# MAX232.net
KiCad netlist of a schematic drawn in Altium Designer
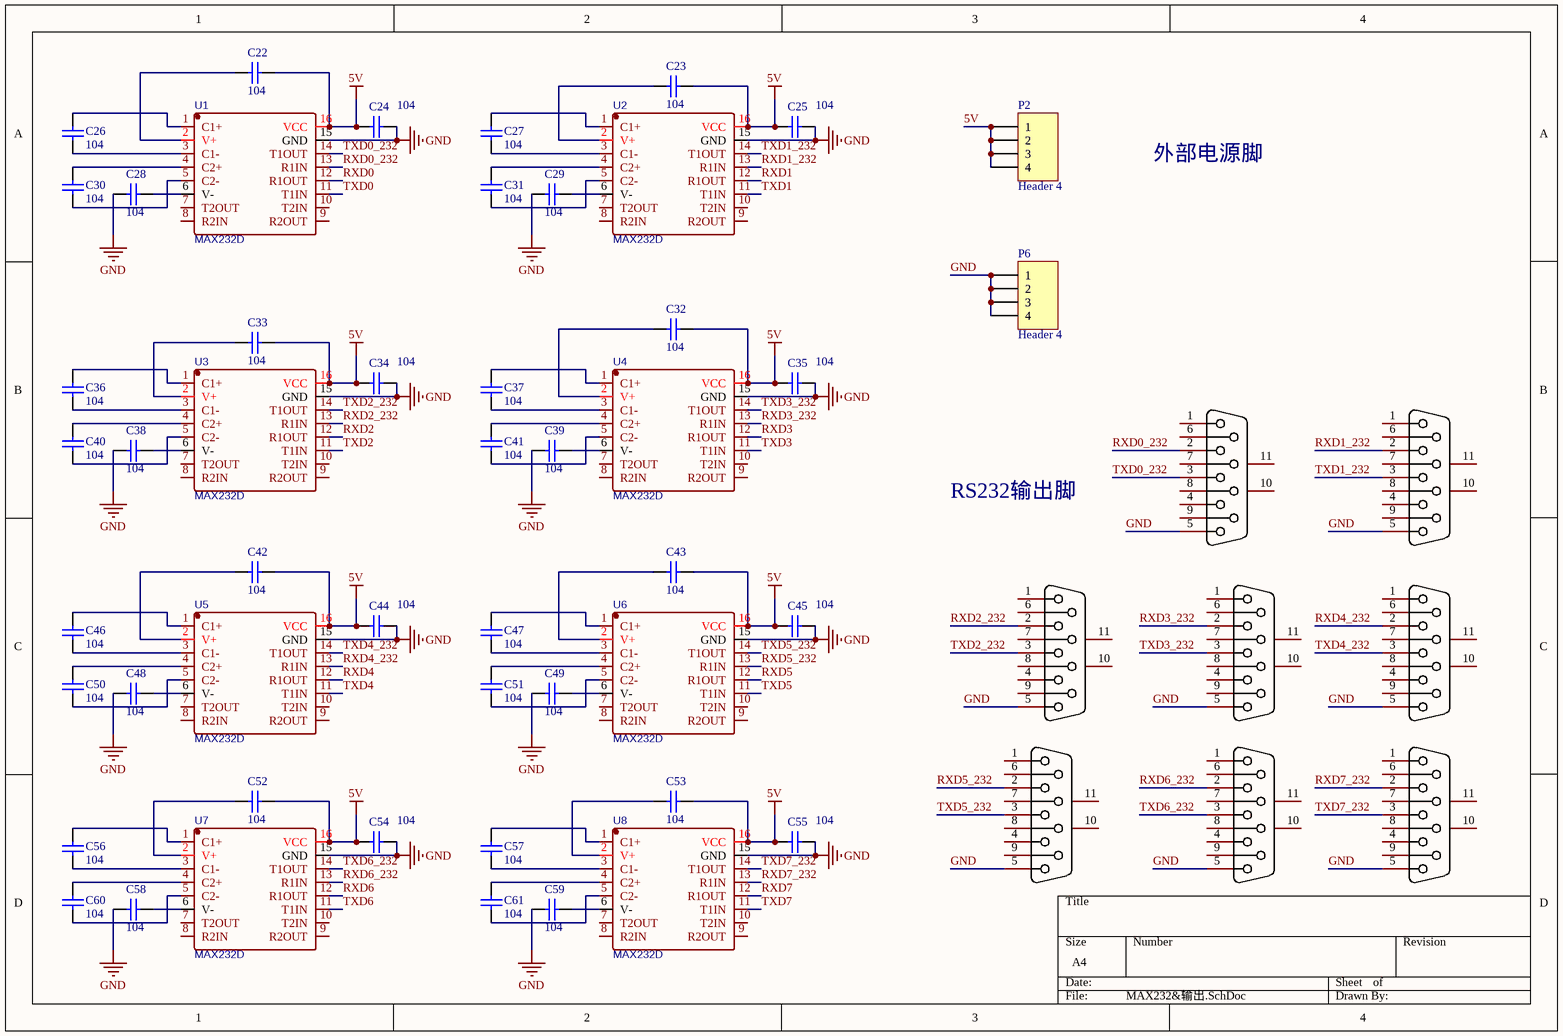
[diagram p0: MAX232&输出.SchDoc]

(export (version "E")
  (design (tool "Eeschema 10.0.6"))
  (components
    (comp (ref "C22")
      (value "104")
      (footprint "0603_C")
      (description "贴片电容")
      (libsource (lib "Miscellaneous Devices LC") (part "0603 100nF (104) 10% 50V"))
    )
    (comp (ref "C23")
      (value "104")
      (footprint "0603_C")
      (description "贴片电容")
      (libsource (lib "Miscellaneous Devices LC") (part "0603 100nF (104) 10% 50V"))
    )
    (comp (ref "C24")
      (value "104")
      (footprint "0603_C")
      (description "贴片电容")
      (libsource (lib "Miscellaneous Devices LC") (part "0603 100nF (104) 10% 50V"))
    )
    (comp (ref "C25")
      (value "104")
      (footprint "0603_C")
      (description "贴片电容")
      (libsource (lib "Miscellaneous Devices LC") (part "0603 100nF (104) 10% 50V"))
    )
    (comp (ref "C26")
      (value "104")
      (footprint "0603_C")
      (description "贴片电容")
      (libsource (lib "Miscellaneous Devices LC") (part "0603 100nF (104) 10% 50V"))
    )
    (comp (ref "C27")
      (value "104")
      (footprint "0603_C")
      (description "贴片电容")
      (libsource (lib "Miscellaneous Devices LC") (part "0603 100nF (104) 10% 50V"))
    )
    (comp (ref "C28")
      (value "104")
      (footprint "0603_C")
      (description "贴片电容")
      (libsource (lib "Miscellaneous Devices LC") (part "0603 100nF (104) 10% 50V"))
    )
    (comp (ref "C29")
      (value "104")
      (footprint "0603_C")
      (description "贴片电容")
      (libsource (lib "Miscellaneous Devices LC") (part "0603 100nF (104) 10% 50V"))
    )
    (comp (ref "C30")
      (value "104")
      (footprint "0603_C")
      (description "贴片电容")
      (libsource (lib "Miscellaneous Devices LC") (part "0603 100nF (104) 10% 50V"))
    )
    (comp (ref "C31")
      (value "104")
      (footprint "0603_C")
      (description "贴片电容")
      (libsource (lib "Miscellaneous Devices LC") (part "0603 100nF (104) 10% 50V"))
    )
    (comp (ref "C32")
      (value "104")
      (footprint "0603_C")
      (description "贴片电容")
      (libsource (lib "Miscellaneous Devices LC") (part "0603 100nF (104) 10% 50V"))
    )
    (comp (ref "C33")
      (value "104")
      (footprint "0603_C")
      (description "贴片电容")
      (libsource (lib "Miscellaneous Devices LC") (part "0603 100nF (104) 10% 50V"))
    )
    (comp (ref "C34")
      (value "104")
      (footprint "0603_C")
      (description "贴片电容")
      (libsource (lib "Miscellaneous Devices LC") (part "0603 100nF (104) 10% 50V"))
    )
    (comp (ref "C35")
      (value "104")
      (footprint "0603_C")
      (description "贴片电容")
      (libsource (lib "Miscellaneous Devices LC") (part "0603 100nF (104) 10% 50V"))
    )
    (comp (ref "C36")
      (value "104")
      (footprint "0603_C")
      (description "贴片电容")
      (libsource (lib "Miscellaneous Devices LC") (part "0603 100nF (104) 10% 50V"))
    )
    (comp (ref "C37")
      (value "104")
      (footprint "0603_C")
      (description "贴片电容")
      (libsource (lib "Miscellaneous Devices LC") (part "0603 100nF (104) 10% 50V"))
    )
    (comp (ref "C38")
      (value "104")
      (footprint "0603_C")
      (description "贴片电容")
      (libsource (lib "Miscellaneous Devices LC") (part "0603 100nF (104) 10% 50V"))
    )
    (comp (ref "C39")
      (value "104")
      (footprint "0603_C")
      (description "贴片电容")
      (libsource (lib "Miscellaneous Devices LC") (part "0603 100nF (104) 10% 50V"))
    )
    (comp (ref "C40")
      (value "104")
      (footprint "0603_C")
      (description "贴片电容")
      (libsource (lib "Miscellaneous Devices LC") (part "0603 100nF (104) 10% 50V"))
    )
    (comp (ref "C41")
      (value "104")
      (footprint "0603_C")
      (description "贴片电容")
      (libsource (lib "Miscellaneous Devices LC") (part "0603 100nF (104) 10% 50V"))
    )
    (comp (ref "C42")
      (value "104")
      (footprint "0603_C")
      (description "贴片电容")
      (libsource (lib "Miscellaneous Devices LC") (part "0603 100nF (104) 10% 50V"))
    )
    (comp (ref "C43")
      (value "104")
      (footprint "0603_C")
      (description "贴片电容")
      (libsource (lib "Miscellaneous Devices LC") (part "0603 100nF (104) 10% 50V"))
    )
    (comp (ref "C44")
      (value "104")
      (footprint "0603_C")
      (description "贴片电容")
      (libsource (lib "Miscellaneous Devices LC") (part "0603 100nF (104) 10% 50V"))
    )
    (comp (ref "C45")
      (value "104")
      (footprint "0603_C")
      (description "贴片电容")
      (libsource (lib "Miscellaneous Devices LC") (part "0603 100nF (104) 10% 50V"))
    )
    (comp (ref "C46")
      (value "104")
      (footprint "0603_C")
      (description "贴片电容")
      (libsource (lib "Miscellaneous Devices LC") (part "0603 100nF (104) 10% 50V"))
    )
    (comp (ref "C47")
      (value "104")
      (footprint "0603_C")
      (description "贴片电容")
      (libsource (lib "Miscellaneous Devices LC") (part "0603 100nF (104) 10% 50V"))
    )
    (comp (ref "C48")
      (value "104")
      (footprint "0603_C")
      (description "贴片电容")
      (libsource (lib "Miscellaneous Devices LC") (part "0603 100nF (104) 10% 50V"))
    )
    (comp (ref "C49")
      (value "104")
      (footprint "0603_C")
      (description "贴片电容")
      (libsource (lib "Miscellaneous Devices LC") (part "0603 100nF (104) 10% 50V"))
    )
    (comp (ref "C50")
      (value "104")
      (footprint "0603_C")
      (description "贴片电容")
      (libsource (lib "Miscellaneous Devices LC") (part "0603 100nF (104) 10% 50V"))
    )
    (comp (ref "C51")
      (value "104")
      (footprint "0603_C")
      (description "贴片电容")
      (libsource (lib "Miscellaneous Devices LC") (part "0603 100nF (104) 10% 50V"))
    )
    (comp (ref "C52")
      (value "104")
      (footprint "0603_C")
      (description "贴片电容")
      (libsource (lib "Miscellaneous Devices LC") (part "0603 100nF (104) 10% 50V"))
    )
    (comp (ref "C53")
      (value "104")
      (footprint "0603_C")
      (description "贴片电容")
      (libsource (lib "Miscellaneous Devices LC") (part "0603 100nF (104) 10% 50V"))
    )
    (comp (ref "C54")
      (value "104")
      (footprint "0603_C")
      (description "贴片电容")
      (libsource (lib "Miscellaneous Devices LC") (part "0603 100nF (104) 10% 50V"))
    )
    (comp (ref "C55")
      (value "104")
      (footprint "0603_C")
      (description "贴片电容")
      (libsource (lib "Miscellaneous Devices LC") (part "0603 100nF (104) 10% 50V"))
    )
    (comp (ref "C56")
      (value "104")
      (footprint "0603_C")
      (description "贴片电容")
      (libsource (lib "Miscellaneous Devices LC") (part "0603 100nF (104) 10% 50V"))
    )
    (comp (ref "C57")
      (value "104")
      (footprint "0603_C")
      (description "贴片电容")
      (libsource (lib "Miscellaneous Devices LC") (part "0603 100nF (104) 10% 50V"))
    )
    (comp (ref "C58")
      (value "104")
      (footprint "0603_C")
      (description "贴片电容")
      (libsource (lib "Miscellaneous Devices LC") (part "0603 100nF (104) 10% 50V"))
    )
    (comp (ref "C59")
      (value "104")
      (footprint "0603_C")
      (description "贴片电容")
      (libsource (lib "Miscellaneous Devices LC") (part "0603 100nF (104) 10% 50V"))
    )
    (comp (ref "C60")
      (value "104")
      (footprint "0603_C")
      (description "贴片电容")
      (libsource (lib "Miscellaneous Devices LC") (part "0603 100nF (104) 10% 50V"))
    )
    (comp (ref "C61")
      (value "104")
      (footprint "0603_C")
      (description "贴片电容")
      (libsource (lib "Miscellaneous Devices LC") (part "0603 100nF (104) 10% 50V"))
    )
    (comp (ref "DSUB1")
      (value "D-DMR009PM-D002")
      (footprint "DSUB-TH_DMR-9P")
      (fields (field (name "MANUFACTURER") "Ckmtw(灿科盟)"))
      (libsource (lib "DB9公头") (part "D-DMR009PM-D002"))
    )
    (comp (ref "DSUB2")
      (value "D-DMR009PM-D002")
      (footprint "DSUB-TH_DMR-9P")
      (fields (field (name "MANUFACTURER") "Ckmtw(灿科盟)"))
      (libsource (lib "DB9公头") (part "D-DMR009PM-D002"))
    )
    (comp (ref "DSUB3")
      (value "D-DMR009PM-D002")
      (footprint "DSUB-TH_DMR-9P")
      (fields (field (name "MANUFACTURER") "Ckmtw(灿科盟)"))
      (libsource (lib "DB9公头") (part "D-DMR009PM-D002"))
    )
    (comp (ref "DSUB4")
      (value "D-DMR009PM-D002")
      (footprint "DSUB-TH_DMR-9P")
      (fields (field (name "MANUFACTURER") "Ckmtw(灿科盟)"))
      (libsource (lib "DB9公头") (part "D-DMR009PM-D002"))
    )
    (comp (ref "DSUB5")
      (value "D-DMR009PM-D002")
      (footprint "DSUB-TH_DMR-9P")
      (fields (field (name "MANUFACTURER") "Ckmtw(灿科盟)"))
      (libsource (lib "DB9公头") (part "D-DMR009PM-D002"))
    )
    (comp (ref "DSUB6")
      (value "D-DMR009PM-D002")
      (footprint "DSUB-TH_DMR-9P")
      (fields (field (name "MANUFACTURER") "Ckmtw(灿科盟)"))
      (libsource (lib "DB9公头") (part "D-DMR009PM-D002"))
    )
    (comp (ref "DSUB7")
      (value "D-DMR009PM-D002")
      (footprint "DSUB-TH_DMR-9P")
      (fields (field (name "MANUFACTURER") "Ckmtw(灿科盟)"))
      (libsource (lib "DB9公头") (part "D-DMR009PM-D002"))
    )
    (comp (ref "DSUB8")
      (value "D-DMR009PM-D002")
      (footprint "DSUB-TH_DMR-9P")
      (fields (field (name "MANUFACTURER") "Ckmtw(灿科盟)"))
      (libsource (lib "DB9公头") (part "D-DMR009PM-D002"))
    )
    (comp (ref "P2")
      (value "Header 4")
      (footprint "HDR1X4")
      (description "Header, 4-Pin")
      (fields (field (name "PUBLISHER") "Altium Limited"))
      (libsource (lib "Miscellaneous Connectors") (part "Header 4"))
    )
    (comp (ref "P6")
      (value "Header 4")
      (footprint "HDR1X4")
      (description "Header, 4-Pin")
      (fields (field (name "PUBLISHER") "Altium Limited"))
      (libsource (lib "Miscellaneous Connectors") (part "Header 4"))
    )
    (comp (ref "U1")
      (value "MAX232D")
      (footprint "SOIC-16_L9.9-W3.9-P1.27-LS6.0-BL")
      (fields (field (name "BOM_SUPPLIER PART") "C350552") (field (name "CONTRIBUTOR") "LCSC"))
      (libsource (lib "Integrated_Library") (part "MAX232D"))
    )
    (comp (ref "U2")
      (value "MAX232D")
      (footprint "SOIC-16_L9.9-W3.9-P1.27-LS6.0-BL")
      (fields (field (name "BOM_SUPPLIER PART") "C350552") (field (name "CONTRIBUTOR") "LCSC"))
      (libsource (lib "Integrated_Library") (part "MAX232D"))
    )
    (comp (ref "U3")
      (value "MAX232D")
      (footprint "SOIC-16_L9.9-W3.9-P1.27-LS6.0-BL")
      (fields (field (name "BOM_SUPPLIER PART") "C350552") (field (name "CONTRIBUTOR") "LCSC"))
      (libsource (lib "Integrated_Library") (part "MAX232D"))
    )
    (comp (ref "U4")
      (value "MAX232D")
      (footprint "SOIC-16_L9.9-W3.9-P1.27-LS6.0-BL")
      (fields (field (name "BOM_SUPPLIER PART") "C350552") (field (name "CONTRIBUTOR") "LCSC"))
      (libsource (lib "Integrated_Library") (part "MAX232D"))
    )
    (comp (ref "U5")
      (value "MAX232D")
      (footprint "SOIC-16_L9.9-W3.9-P1.27-LS6.0-BL")
      (fields (field (name "BOM_SUPPLIER PART") "C350552") (field (name "CONTRIBUTOR") "LCSC"))
      (libsource (lib "Integrated_Library") (part "MAX232D"))
    )
    (comp (ref "U6")
      (value "MAX232D")
      (footprint "SOIC-16_L9.9-W3.9-P1.27-LS6.0-BL")
      (fields (field (name "BOM_SUPPLIER PART") "C350552") (field (name "CONTRIBUTOR") "LCSC"))
      (libsource (lib "Integrated_Library") (part "MAX232D"))
    )
    (comp (ref "U7")
      (value "MAX232D")
      (footprint "SOIC-16_L9.9-W3.9-P1.27-LS6.0-BL")
      (fields (field (name "BOM_SUPPLIER PART") "C350552") (field (name "CONTRIBUTOR") "LCSC"))
      (libsource (lib "Integrated_Library") (part "MAX232D"))
    )
    (comp (ref "U8")
      (value "MAX232D")
      (footprint "SOIC-16_L9.9-W3.9-P1.27-LS6.0-BL")
      (fields (field (name "BOM_SUPPLIER PART") "C350552") (field (name "CONTRIBUTOR") "LCSC"))
      (libsource (lib "Integrated_Library") (part "MAX232D"))
    )
  )
  (nets
    (net (code "1") (name "/RXD0") (class "Default")
      (node (ref "U1") (pin "12") (pinfunction "R1OUT_12") (pintype "passive"))
    )
    (net (code "2") (name "/RXD0_232") (class "Default")
      (node (ref "DSUB1") (pin "2") (pinfunction "2_2") (pintype "passive"))
      (node (ref "U1") (pin "13") (pinfunction "R1IN_13") (pintype "passive"))
    )
    (net (code "3") (name "/RXD1") (class "Default")
      (node (ref "U2") (pin "12") (pinfunction "R1OUT_12") (pintype "passive"))
    )
    (net (code "4") (name "/RXD1_232") (class "Default")
      (node (ref "DSUB2") (pin "2") (pinfunction "2_2") (pintype "passive"))
      (node (ref "U2") (pin "13") (pinfunction "R1IN_13") (pintype "passive"))
    )
    (net (code "5") (name "/RXD2") (class "Default")
      (node (ref "U3") (pin "12") (pinfunction "R1OUT_12") (pintype "passive"))
    )
    (net (code "6") (name "/RXD2_232") (class "Default")
      (node (ref "DSUB3") (pin "2") (pinfunction "2_2") (pintype "passive"))
      (node (ref "U3") (pin "13") (pinfunction "R1IN_13") (pintype "passive"))
    )
    (net (code "7") (name "/RXD3") (class "Default")
      (node (ref "U4") (pin "12") (pinfunction "R1OUT_12") (pintype "passive"))
    )
    (net (code "8") (name "/RXD3_232") (class "Default")
      (node (ref "DSUB4") (pin "2") (pinfunction "2_2") (pintype "passive"))
      (node (ref "U4") (pin "13") (pinfunction "R1IN_13") (pintype "passive"))
    )
    (net (code "9") (name "/RXD4") (class "Default")
      (node (ref "U5") (pin "12") (pinfunction "R1OUT_12") (pintype "passive"))
    )
    (net (code "10") (name "/RXD4_232") (class "Default")
      (node (ref "DSUB5") (pin "2") (pinfunction "2_2") (pintype "passive"))
      (node (ref "U5") (pin "13") (pinfunction "R1IN_13") (pintype "passive"))
    )
    (net (code "11") (name "/RXD5") (class "Default")
      (node (ref "U6") (pin "12") (pinfunction "R1OUT_12") (pintype "passive"))
    )
    (net (code "12") (name "/RXD5_232") (class "Default")
      (node (ref "DSUB6") (pin "2") (pinfunction "2_2") (pintype "passive"))
      (node (ref "U6") (pin "13") (pinfunction "R1IN_13") (pintype "passive"))
    )
    (net (code "13") (name "/RXD6") (class "Default")
      (node (ref "U7") (pin "12") (pinfunction "R1OUT_12") (pintype "passive"))
    )
    (net (code "14") (name "/RXD6_232") (class "Default")
      (node (ref "DSUB7") (pin "2") (pinfunction "2_2") (pintype "passive"))
      (node (ref "U7") (pin "13") (pinfunction "R1IN_13") (pintype "passive"))
    )
    (net (code "15") (name "/RXD7") (class "Default")
      (node (ref "U8") (pin "12") (pinfunction "R1OUT_12") (pintype "passive"))
    )
    (net (code "16") (name "/RXD7_232") (class "Default")
      (node (ref "DSUB8") (pin "2") (pinfunction "2_2") (pintype "passive"))
      (node (ref "U8") (pin "13") (pinfunction "R1IN_13") (pintype "passive"))
    )
    (net (code "17") (name "/TXD0") (class "Default")
      (node (ref "U1") (pin "11") (pinfunction "T1IN_11") (pintype "passive"))
    )
    (net (code "18") (name "/TXD0_232") (class "Default")
      (node (ref "DSUB1") (pin "3") (pinfunction "3_3") (pintype "passive"))
      (node (ref "U1") (pin "14") (pinfunction "T1OUT_14") (pintype "passive"))
    )
    (net (code "19") (name "/TXD1") (class "Default")
      (node (ref "U2") (pin "11") (pinfunction "T1IN_11") (pintype "passive"))
    )
    (net (code "20") (name "/TXD1_232") (class "Default")
      (node (ref "DSUB2") (pin "3") (pinfunction "3_3") (pintype "passive"))
      (node (ref "U2") (pin "14") (pinfunction "T1OUT_14") (pintype "passive"))
    )
    (net (code "21") (name "/TXD2") (class "Default")
      (node (ref "U3") (pin "11") (pinfunction "T1IN_11") (pintype "passive"))
    )
    (net (code "22") (name "/TXD2_232") (class "Default")
      (node (ref "DSUB3") (pin "3") (pinfunction "3_3") (pintype "passive"))
      (node (ref "U3") (pin "14") (pinfunction "T1OUT_14") (pintype "passive"))
    )
    (net (code "23") (name "/TXD3") (class "Default")
      (node (ref "U4") (pin "11") (pinfunction "T1IN_11") (pintype "passive"))
    )
    (net (code "24") (name "/TXD3_232") (class "Default")
      (node (ref "DSUB4") (pin "3") (pinfunction "3_3") (pintype "passive"))
      (node (ref "U4") (pin "14") (pinfunction "T1OUT_14") (pintype "passive"))
    )
    (net (code "25") (name "/TXD4") (class "Default")
      (node (ref "U5") (pin "11") (pinfunction "T1IN_11") (pintype "passive"))
    )
    (net (code "26") (name "/TXD4_232") (class "Default")
      (node (ref "DSUB5") (pin "3") (pinfunction "3_3") (pintype "passive"))
      (node (ref "U5") (pin "14") (pinfunction "T1OUT_14") (pintype "passive"))
    )
    (net (code "27") (name "/TXD5") (class "Default")
      (node (ref "U6") (pin "11") (pinfunction "T1IN_11") (pintype "passive"))
    )
    (net (code "28") (name "/TXD5_232") (class "Default")
      (node (ref "DSUB6") (pin "3") (pinfunction "3_3") (pintype "passive"))
      (node (ref "U6") (pin "14") (pinfunction "T1OUT_14") (pintype "passive"))
    )
    (net (code "29") (name "/TXD6") (class "Default")
      (node (ref "U7") (pin "11") (pinfunction "T1IN_11") (pintype "passive"))
    )
    (net (code "30") (name "/TXD6_232") (class "Default")
      (node (ref "DSUB7") (pin "3") (pinfunction "3_3") (pintype "passive"))
      (node (ref "U7") (pin "14") (pinfunction "T1OUT_14") (pintype "passive"))
    )
    (net (code "31") (name "/TXD7") (class "Default")
      (node (ref "U8") (pin "11") (pinfunction "T1IN_11") (pintype "passive"))
    )
    (net (code "32") (name "/TXD7_232") (class "Default")
      (node (ref "DSUB8") (pin "3") (pinfunction "3_3") (pintype "passive"))
      (node (ref "U8") (pin "14") (pinfunction "T1OUT_14") (pintype "passive"))
    )
    (net (code "33") (name "5V") (class "Default")
      (node (ref "C22") (pin "1") (pinfunction "1_1") (pintype "passive"))
      (node (ref "C23") (pin "1") (pinfunction "1_1") (pintype "passive"))
      (node (ref "C24") (pin "1") (pinfunction "1_1") (pintype "passive"))
      (node (ref "C25") (pin "1") (pinfunction "1_1") (pintype "passive"))
      (node (ref "C32") (pin "1") (pinfunction "1_1") (pintype "passive"))
      (node (ref "C33") (pin "1") (pinfunction "1_1") (pintype "passive"))
      (node (ref "C34") (pin "1") (pinfunction "1_1") (pintype "passive"))
      (node (ref "C35") (pin "1") (pinfunction "1_1") (pintype "passive"))
      (node (ref "C42") (pin "1") (pinfunction "1_1") (pintype "passive"))
      (node (ref "C43") (pin "1") (pinfunction "1_1") (pintype "passive"))
      (node (ref "C44") (pin "1") (pinfunction "1_1") (pintype "passive"))
      (node (ref "C45") (pin "1") (pinfunction "1_1") (pintype "passive"))
      (node (ref "C52") (pin "1") (pinfunction "1_1") (pintype "passive"))
      (node (ref "C53") (pin "1") (pinfunction "1_1") (pintype "passive"))
      (node (ref "C54") (pin "1") (pinfunction "1_1") (pintype "passive"))
      (node (ref "C55") (pin "1") (pinfunction "1_1") (pintype "passive"))
      (node (ref "P2") (pin "1") (pinfunction "1_1") (pintype "passive"))
      (node (ref "P2") (pin "2") (pinfunction "2_2") (pintype "passive"))
      (node (ref "P2") (pin "3") (pinfunction "3_3") (pintype "passive"))
      (node (ref "P2") (pin "4") (pinfunction "4_4") (pintype "passive"))
      (node (ref "U1") (pin "16") (pinfunction "VCC_16") (pintype "passive"))
      (node (ref "U2") (pin "16") (pinfunction "VCC_16") (pintype "passive"))
      (node (ref "U3") (pin "16") (pinfunction "VCC_16") (pintype "passive"))
      (node (ref "U4") (pin "16") (pinfunction "VCC_16") (pintype "passive"))
      (node (ref "U5") (pin "16") (pinfunction "VCC_16") (pintype "passive"))
      (node (ref "U6") (pin "16") (pinfunction "VCC_16") (pintype "passive"))
      (node (ref "U7") (pin "16") (pinfunction "VCC_16") (pintype "passive"))
      (node (ref "U8") (pin "16") (pinfunction "VCC_16") (pintype "passive"))
    )
    (net (code "34") (name "GND") (class "Default")
      (node (ref "C24") (pin "2") (pinfunction "2_2") (pintype "passive"))
      (node (ref "C25") (pin "2") (pinfunction "2_2") (pintype "passive"))
      (node (ref "C28") (pin "1") (pinfunction "1_1") (pintype "passive"))
      (node (ref "C29") (pin "1") (pinfunction "1_1") (pintype "passive"))
      (node (ref "C34") (pin "2") (pinfunction "2_2") (pintype "passive"))
      (node (ref "C35") (pin "2") (pinfunction "2_2") (pintype "passive"))
      (node (ref "C38") (pin "1") (pinfunction "1_1") (pintype "passive"))
      (node (ref "C39") (pin "1") (pinfunction "1_1") (pintype "passive"))
      (node (ref "C44") (pin "2") (pinfunction "2_2") (pintype "passive"))
      (node (ref "C45") (pin "2") (pinfunction "2_2") (pintype "passive"))
      (node (ref "C48") (pin "1") (pinfunction "1_1") (pintype "passive"))
      (node (ref "C49") (pin "1") (pinfunction "1_1") (pintype "passive"))
      (node (ref "C54") (pin "2") (pinfunction "2_2") (pintype "passive"))
      (node (ref "C55") (pin "2") (pinfunction "2_2") (pintype "passive"))
      (node (ref "C58") (pin "1") (pinfunction "1_1") (pintype "passive"))
      (node (ref "C59") (pin "1") (pinfunction "1_1") (pintype "passive"))
      (node (ref "DSUB1") (pin "5") (pinfunction "5_5") (pintype "passive"))
      (node (ref "DSUB2") (pin "5") (pinfunction "5_5") (pintype "passive"))
      (node (ref "DSUB3") (pin "5") (pinfunction "5_5") (pintype "passive"))
      (node (ref "DSUB4") (pin "5") (pinfunction "5_5") (pintype "passive"))
      (node (ref "DSUB5") (pin "5") (pinfunction "5_5") (pintype "passive"))
      (node (ref "DSUB6") (pin "5") (pinfunction "5_5") (pintype "passive"))
      (node (ref "DSUB7") (pin "5") (pinfunction "5_5") (pintype "passive"))
      (node (ref "DSUB8") (pin "5") (pinfunction "5_5") (pintype "passive"))
      (node (ref "P6") (pin "1") (pinfunction "1_1") (pintype "passive"))
      (node (ref "P6") (pin "2") (pinfunction "2_2") (pintype "passive"))
      (node (ref "P6") (pin "3") (pinfunction "3_3") (pintype "passive"))
      (node (ref "P6") (pin "4") (pinfunction "4_4") (pintype "passive"))
      (node (ref "U1") (pin "15") (pinfunction "GND_15") (pintype "passive"))
      (node (ref "U2") (pin "15") (pinfunction "GND_15") (pintype "passive"))
      (node (ref "U3") (pin "15") (pinfunction "GND_15") (pintype "passive"))
      (node (ref "U4") (pin "15") (pinfunction "GND_15") (pintype "passive"))
      (node (ref "U5") (pin "15") (pinfunction "GND_15") (pintype "passive"))
      (node (ref "U6") (pin "15") (pinfunction "GND_15") (pintype "passive"))
      (node (ref "U7") (pin "15") (pinfunction "GND_15") (pintype "passive"))
      (node (ref "U8") (pin "15") (pinfunction "GND_15") (pintype "passive"))
    )
    (net (code "35") (name "Net-(U1-C1+)") (class "Default")
      (node (ref "C26") (pin "2") (pinfunction "2_2") (pintype "passive"))
      (node (ref "U1") (pin "1") (pinfunction "C1+_1") (pintype "passive"))
    )
    (net (code "36") (name "Net-(U1-C1-)") (class "Default")
      (node (ref "C26") (pin "1") (pinfunction "1_1") (pintype "passive"))
      (node (ref "U1") (pin "3") (pinfunction "C1-_3") (pintype "passive"))
    )
    (net (code "37") (name "Net-(U1-C2+)") (class "Default")
      (node (ref "C30") (pin "2") (pinfunction "2_2") (pintype "passive"))
      (node (ref "U1") (pin "4") (pinfunction "C2+_4") (pintype "passive"))
    )
    (net (code "38") (name "Net-(U1-C2-)") (class "Default")
      (node (ref "C30") (pin "1") (pinfunction "1_1") (pintype "passive"))
      (node (ref "U1") (pin "5") (pinfunction "C2-_5") (pintype "passive"))
    )
    (net (code "39") (name "Net-(U1-V+)") (class "Default")
      (node (ref "C22") (pin "2") (pinfunction "2_2") (pintype "passive"))
      (node (ref "U1") (pin "2") (pinfunction "V+_2") (pintype "passive"))
    )
    (net (code "40") (name "Net-(U1-V-)") (class "Default")
      (node (ref "C28") (pin "2") (pinfunction "2_2") (pintype "passive"))
      (node (ref "U1") (pin "6") (pinfunction "V-_6") (pintype "passive"))
    )
    (net (code "41") (name "Net-(U2-C1+)") (class "Default")
      (node (ref "C27") (pin "2") (pinfunction "2_2") (pintype "passive"))
      (node (ref "U2") (pin "1") (pinfunction "C1+_1") (pintype "passive"))
    )
    (net (code "42") (name "Net-(U2-C1-)") (class "Default")
      (node (ref "C27") (pin "1") (pinfunction "1_1") (pintype "passive"))
      (node (ref "U2") (pin "3") (pinfunction "C1-_3") (pintype "passive"))
    )
    (net (code "43") (name "Net-(U2-C2+)") (class "Default")
      (node (ref "C31") (pin "2") (pinfunction "2_2") (pintype "passive"))
      (node (ref "U2") (pin "4") (pinfunction "C2+_4") (pintype "passive"))
    )
    (net (code "44") (name "Net-(U2-C2-)") (class "Default")
      (node (ref "C31") (pin "1") (pinfunction "1_1") (pintype "passive"))
      (node (ref "U2") (pin "5") (pinfunction "C2-_5") (pintype "passive"))
    )
    (net (code "45") (name "Net-(U2-V+)") (class "Default")
      (node (ref "C23") (pin "2") (pinfunction "2_2") (pintype "passive"))
      (node (ref "U2") (pin "2") (pinfunction "V+_2") (pintype "passive"))
    )
    (net (code "46") (name "Net-(U2-V-)") (class "Default")
      (node (ref "C29") (pin "2") (pinfunction "2_2") (pintype "passive"))
      (node (ref "U2") (pin "6") (pinfunction "V-_6") (pintype "passive"))
    )
    (net (code "47") (name "Net-(U3-C1+)") (class "Default")
      (node (ref "C36") (pin "2") (pinfunction "2_2") (pintype "passive"))
      (node (ref "U3") (pin "1") (pinfunction "C1+_1") (pintype "passive"))
    )
    (net (code "48") (name "Net-(U3-C1-)") (class "Default")
      (node (ref "C36") (pin "1") (pinfunction "1_1") (pintype "passive"))
      (node (ref "U3") (pin "3") (pinfunction "C1-_3") (pintype "passive"))
    )
    (net (code "49") (name "Net-(U3-C2+)") (class "Default")
      (node (ref "C40") (pin "2") (pinfunction "2_2") (pintype "passive"))
      (node (ref "U3") (pin "4") (pinfunction "C2+_4") (pintype "passive"))
    )
    (net (code "50") (name "Net-(U3-C2-)") (class "Default")
      (node (ref "C40") (pin "1") (pinfunction "1_1") (pintype "passive"))
      (node (ref "U3") (pin "5") (pinfunction "C2-_5") (pintype "passive"))
    )
    (net (code "51") (name "Net-(U3-V+)") (class "Default")
      (node (ref "C33") (pin "2") (pinfunction "2_2") (pintype "passive"))
      (node (ref "U3") (pin "2") (pinfunction "V+_2") (pintype "passive"))
    )
    (net (code "52") (name "Net-(U3-V-)") (class "Default")
      (node (ref "C38") (pin "2") (pinfunction "2_2") (pintype "passive"))
      (node (ref "U3") (pin "6") (pinfunction "V-_6") (pintype "passive"))
    )
    (net (code "53") (name "Net-(U4-C1+)") (class "Default")
      (node (ref "C37") (pin "2") (pinfunction "2_2") (pintype "passive"))
      (node (ref "U4") (pin "1") (pinfunction "C1+_1") (pintype "passive"))
    )
    (net (code "54") (name "Net-(U4-C1-)") (class "Default")
      (node (ref "C37") (pin "1") (pinfunction "1_1") (pintype "passive"))
      (node (ref "U4") (pin "3") (pinfunction "C1-_3") (pintype "passive"))
    )
    (net (code "55") (name "Net-(U4-C2+)") (class "Default")
      (node (ref "C41") (pin "2") (pinfunction "2_2") (pintype "passive"))
      (node (ref "U4") (pin "4") (pinfunction "C2+_4") (pintype "passive"))
    )
    (net (code "56") (name "Net-(U4-C2-)") (class "Default")
      (node (ref "C41") (pin "1") (pinfunction "1_1") (pintype "passive"))
      (node (ref "U4") (pin "5") (pinfunction "C2-_5") (pintype "passive"))
    )
    (net (code "57") (name "Net-(U4-V+)") (class "Default")
      (node (ref "C32") (pin "2") (pinfunction "2_2") (pintype "passive"))
      (node (ref "U4") (pin "2") (pinfunction "V+_2") (pintype "passive"))
    )
    (net (code "58") (name "Net-(U4-V-)") (class "Default")
      (node (ref "C39") (pin "2") (pinfunction "2_2") (pintype "passive"))
      (node (ref "U4") (pin "6") (pinfunction "V-_6") (pintype "passive"))
    )
    (net (code "59") (name "Net-(U5-C1+)") (class "Default")
      (node (ref "C46") (pin "2") (pinfunction "2_2") (pintype "passive"))
      (node (ref "U5") (pin "1") (pinfunction "C1+_1") (pintype "passive"))
    )
    (net (code "60") (name "Net-(U5-C1-)") (class "Default")
      (node (ref "C46") (pin "1") (pinfunction "1_1") (pintype "passive"))
      (node (ref "U5") (pin "3") (pinfunction "C1-_3") (pintype "passive"))
    )
    (net (code "61") (name "Net-(U5-C2+)") (class "Default")
      (node (ref "C50") (pin "2") (pinfunction "2_2") (pintype "passive"))
      (node (ref "U5") (pin "4") (pinfunction "C2+_4") (pintype "passive"))
    )
    (net (code "62") (name "Net-(U5-C2-)") (class "Default")
      (node (ref "C50") (pin "1") (pinfunction "1_1") (pintype "passive"))
      (node (ref "U5") (pin "5") (pinfunction "C2-_5") (pintype "passive"))
    )
    (net (code "63") (name "Net-(U5-V+)") (class "Default")
      (node (ref "C42") (pin "2") (pinfunction "2_2") (pintype "passive"))
      (node (ref "U5") (pin "2") (pinfunction "V+_2") (pintype "passive"))
    )
    (net (code "64") (name "Net-(U5-V-)") (class "Default")
      (node (ref "C48") (pin "2") (pinfunction "2_2") (pintype "passive"))
      (node (ref "U5") (pin "6") (pinfunction "V-_6") (pintype "passive"))
    )
    (net (code "65") (name "Net-(U6-C1+)") (class "Default")
      (node (ref "C47") (pin "2") (pinfunction "2_2") (pintype "passive"))
      (node (ref "U6") (pin "1") (pinfunction "C1+_1") (pintype "passive"))
    )
    (net (code "66") (name "Net-(U6-C1-)") (class "Default")
      (node (ref "C47") (pin "1") (pinfunction "1_1") (pintype "passive"))
      (node (ref "U6") (pin "3") (pinfunction "C1-_3") (pintype "passive"))
    )
    (net (code "67") (name "Net-(U6-C2+)") (class "Default")
      (node (ref "C51") (pin "2") (pinfunction "2_2") (pintype "passive"))
      (node (ref "U6") (pin "4") (pinfunction "C2+_4") (pintype "passive"))
    )
    (net (code "68") (name "Net-(U6-C2-)") (class "Default")
      (node (ref "C51") (pin "1") (pinfunction "1_1") (pintype "passive"))
      (node (ref "U6") (pin "5") (pinfunction "C2-_5") (pintype "passive"))
    )
    (net (code "69") (name "Net-(U6-V+)") (class "Default")
      (node (ref "C43") (pin "2") (pinfunction "2_2") (pintype "passive"))
      (node (ref "U6") (pin "2") (pinfunction "V+_2") (pintype "passive"))
    )
    (net (code "70") (name "Net-(U6-V-)") (class "Default")
      (node (ref "C49") (pin "2") (pinfunction "2_2") (pintype "passive"))
      (node (ref "U6") (pin "6") (pinfunction "V-_6") (pintype "passive"))
    )
    (net (code "71") (name "Net-(U7-C1+)") (class "Default")
      (node (ref "C56") (pin "2") (pinfunction "2_2") (pintype "passive"))
      (node (ref "U7") (pin "1") (pinfunction "C1+_1") (pintype "passive"))
    )
    (net (code "72") (name "Net-(U7-C1-)") (class "Default")
      (node (ref "C56") (pin "1") (pinfunction "1_1") (pintype "passive"))
      (node (ref "U7") (pin "3") (pinfunction "C1-_3") (pintype "passive"))
    )
    (net (code "73") (name "Net-(U7-C2+)") (class "Default")
      (node (ref "C60") (pin "2") (pinfunction "2_2") (pintype "passive"))
      (node (ref "U7") (pin "4") (pinfunction "C2+_4") (pintype "passive"))
    )
    (net (code "74") (name "Net-(U7-C2-)") (class "Default")
      (node (ref "C60") (pin "1") (pinfunction "1_1") (pintype "passive"))
      (node (ref "U7") (pin "5") (pinfunction "C2-_5") (pintype "passive"))
    )
    (net (code "75") (name "Net-(U7-V+)") (class "Default")
      (node (ref "C52") (pin "2") (pinfunction "2_2") (pintype "passive"))
      (node (ref "U7") (pin "2") (pinfunction "V+_2") (pintype "passive"))
    )
    (net (code "76") (name "Net-(U7-V-)") (class "Default")
      (node (ref "C58") (pin "2") (pinfunction "2_2") (pintype "passive"))
      (node (ref "U7") (pin "6") (pinfunction "V-_6") (pintype "passive"))
    )
    (net (code "77") (name "Net-(U8-C1+)") (class "Default")
      (node (ref "C57") (pin "2") (pinfunction "2_2") (pintype "passive"))
      (node (ref "U8") (pin "1") (pinfunction "C1+_1") (pintype "passive"))
    )
    (net (code "78") (name "Net-(U8-C1-)") (class "Default")
      (node (ref "C57") (pin "1") (pinfunction "1_1") (pintype "passive"))
      (node (ref "U8") (pin "3") (pinfunction "C1-_3") (pintype "passive"))
    )
    (net (code "79") (name "Net-(U8-C2+)") (class "Default")
      (node (ref "C61") (pin "2") (pinfunction "2_2") (pintype "passive"))
      (node (ref "U8") (pin "4") (pinfunction "C2+_4") (pintype "passive"))
    )
    (net (code "80") (name "Net-(U8-C2-)") (class "Default")
      (node (ref "C61") (pin "1") (pinfunction "1_1") (pintype "passive"))
      (node (ref "U8") (pin "5") (pinfunction "C2-_5") (pintype "passive"))
    )
    (net (code "81") (name "Net-(U8-V+)") (class "Default")
      (node (ref "C53") (pin "2") (pinfunction "2_2") (pintype "passive"))
      (node (ref "U8") (pin "2") (pinfunction "V+_2") (pintype "passive"))
    )
    (net (code "82") (name "Net-(U8-V-)") (class "Default")
      (node (ref "C59") (pin "2") (pinfunction "2_2") (pintype "passive"))
      (node (ref "U8") (pin "6") (pinfunction "V-_6") (pintype "passive"))
    )
    (net (code "83") (name "unconnected-(DSUB1-MH1-Pad10)") (class "Default")
      (node (ref "DSUB1") (pin "10") (pinfunction "MH1_10") (pintype "passive"))
    )
    (net (code "84") (name "unconnected-(DSUB1-MH2-Pad11)") (class "Default")
      (node (ref "DSUB1") (pin "11") (pinfunction "MH2_11") (pintype "passive"))
    )
    (net (code "85") (name "unconnected-(DSUB1-Pad1)") (class "Default")
      (node (ref "DSUB1") (pin "1") (pinfunction "1_1") (pintype "passive"))
    )
    (net (code "86") (name "unconnected-(DSUB1-Pad4)") (class "Default")
      (node (ref "DSUB1") (pin "4") (pinfunction "4_4") (pintype "passive"))
    )
    (net (code "87") (name "unconnected-(DSUB1-Pad6)") (class "Default")
      (node (ref "DSUB1") (pin "6") (pinfunction "6_6") (pintype "passive"))
    )
    (net (code "88") (name "unconnected-(DSUB1-Pad7)") (class "Default")
      (node (ref "DSUB1") (pin "7") (pinfunction "7_7") (pintype "passive"))
    )
    (net (code "89") (name "unconnected-(DSUB1-Pad8)") (class "Default")
      (node (ref "DSUB1") (pin "8") (pinfunction "8_8") (pintype "passive"))
    )
    (net (code "90") (name "unconnected-(DSUB1-Pad9)") (class "Default")
      (node (ref "DSUB1") (pin "9") (pinfunction "9_9") (pintype "passive"))
    )
    (net (code "91") (name "unconnected-(DSUB2-MH1-Pad10)") (class "Default")
      (node (ref "DSUB2") (pin "10") (pinfunction "MH1_10") (pintype "passive"))
    )
    (net (code "92") (name "unconnected-(DSUB2-MH2-Pad11)") (class "Default")
      (node (ref "DSUB2") (pin "11") (pinfunction "MH2_11") (pintype "passive"))
    )
    (net (code "93") (name "unconnected-(DSUB2-Pad1)") (class "Default")
      (node (ref "DSUB2") (pin "1") (pinfunction "1_1") (pintype "passive"))
    )
    (net (code "94") (name "unconnected-(DSUB2-Pad4)") (class "Default")
      (node (ref "DSUB2") (pin "4") (pinfunction "4_4") (pintype "passive"))
    )
    (net (code "95") (name "unconnected-(DSUB2-Pad6)") (class "Default")
      (node (ref "DSUB2") (pin "6") (pinfunction "6_6") (pintype "passive"))
    )
    (net (code "96") (name "unconnected-(DSUB2-Pad7)") (class "Default")
      (node (ref "DSUB2") (pin "7") (pinfunction "7_7") (pintype "passive"))
    )
    (net (code "97") (name "unconnected-(DSUB2-Pad8)") (class "Default")
      (node (ref "DSUB2") (pin "8") (pinfunction "8_8") (pintype "passive"))
    )
    (net (code "98") (name "unconnected-(DSUB2-Pad9)") (class "Default")
      (node (ref "DSUB2") (pin "9") (pinfunction "9_9") (pintype "passive"))
    )
    (net (code "99") (name "unconnected-(DSUB3-MH1-Pad10)") (class "Default")
      (node (ref "DSUB3") (pin "10") (pinfunction "MH1_10") (pintype "passive"))
    )
    (net (code "100") (name "unconnected-(DSUB3-MH2-Pad11)") (class "Default")
      (node (ref "DSUB3") (pin "11") (pinfunction "MH2_11") (pintype "passive"))
    )
    (net (code "101") (name "unconnected-(DSUB3-Pad1)") (class "Default")
      (node (ref "DSUB3") (pin "1") (pinfunction "1_1") (pintype "passive"))
    )
    (net (code "102") (name "unconnected-(DSUB3-Pad4)") (class "Default")
      (node (ref "DSUB3") (pin "4") (pinfunction "4_4") (pintype "passive"))
    )
    (net (code "103") (name "unconnected-(DSUB3-Pad6)") (class "Default")
      (node (ref "DSUB3") (pin "6") (pinfunction "6_6") (pintype "passive"))
    )
    (net (code "104") (name "unconnected-(DSUB3-Pad7)") (class "Default")
      (node (ref "DSUB3") (pin "7") (pinfunction "7_7") (pintype "passive"))
    )
    (net (code "105") (name "unconnected-(DSUB3-Pad8)") (class "Default")
      (node (ref "DSUB3") (pin "8") (pinfunction "8_8") (pintype "passive"))
    )
    (net (code "106") (name "unconnected-(DSUB3-Pad9)") (class "Default")
      (node (ref "DSUB3") (pin "9") (pinfunction "9_9") (pintype "passive"))
    )
    (net (code "107") (name "unconnected-(DSUB4-MH1-Pad10)") (class "Default")
      (node (ref "DSUB4") (pin "10") (pinfunction "MH1_10") (pintype "passive"))
    )
    (net (code "108") (name "unconnected-(DSUB4-MH2-Pad11)") (class "Default")
      (node (ref "DSUB4") (pin "11") (pinfunction "MH2_11") (pintype "passive"))
    )
    (net (code "109") (name "unconnected-(DSUB4-Pad1)") (class "Default")
      (node (ref "DSUB4") (pin "1") (pinfunction "1_1") (pintype "passive"))
    )
    (net (code "110") (name "unconnected-(DSUB4-Pad4)") (class "Default")
      (node (ref "DSUB4") (pin "4") (pinfunction "4_4") (pintype "passive"))
    )
    (net (code "111") (name "unconnected-(DSUB4-Pad6)") (class "Default")
      (node (ref "DSUB4") (pin "6") (pinfunction "6_6") (pintype "passive"))
    )
    (net (code "112") (name "unconnected-(DSUB4-Pad7)") (class "Default")
      (node (ref "DSUB4") (pin "7") (pinfunction "7_7") (pintype "passive"))
    )
    (net (code "113") (name "unconnected-(DSUB4-Pad8)") (class "Default")
      (node (ref "DSUB4") (pin "8") (pinfunction "8_8") (pintype "passive"))
    )
    (net (code "114") (name "unconnected-(DSUB4-Pad9)") (class "Default")
      (node (ref "DSUB4") (pin "9") (pinfunction "9_9") (pintype "passive"))
    )
    (net (code "115") (name "unconnected-(DSUB5-MH1-Pad10)") (class "Default")
      (node (ref "DSUB5") (pin "10") (pinfunction "MH1_10") (pintype "passive"))
    )
    (net (code "116") (name "unconnected-(DSUB5-MH2-Pad11)") (class "Default")
      (node (ref "DSUB5") (pin "11") (pinfunction "MH2_11") (pintype "passive"))
    )
    (net (code "117") (name "unconnected-(DSUB5-Pad1)") (class "Default")
      (node (ref "DSUB5") (pin "1") (pinfunction "1_1") (pintype "passive"))
    )
    (net (code "118") (name "unconnected-(DSUB5-Pad4)") (class "Default")
      (node (ref "DSUB5") (pin "4") (pinfunction "4_4") (pintype "passive"))
    )
    (net (code "119") (name "unconnected-(DSUB5-Pad6)") (class "Default")
      (node (ref "DSUB5") (pin "6") (pinfunction "6_6") (pintype "passive"))
    )
    (net (code "120") (name "unconnected-(DSUB5-Pad7)") (class "Default")
      (node (ref "DSUB5") (pin "7") (pinfunction "7_7") (pintype "passive"))
    )
    (net (code "121") (name "unconnected-(DSUB5-Pad8)") (class "Default")
      (node (ref "DSUB5") (pin "8") (pinfunction "8_8") (pintype "passive"))
    )
    (net (code "122") (name "unconnected-(DSUB5-Pad9)") (class "Default")
      (node (ref "DSUB5") (pin "9") (pinfunction "9_9") (pintype "passive"))
    )
    (net (code "123") (name "unconnected-(DSUB6-MH1-Pad10)") (class "Default")
      (node (ref "DSUB6") (pin "10") (pinfunction "MH1_10") (pintype "passive"))
    )
    (net (code "124") (name "unconnected-(DSUB6-MH2-Pad11)") (class "Default")
      (node (ref "DSUB6") (pin "11") (pinfunction "MH2_11") (pintype "passive"))
    )
    (net (code "125") (name "unconnected-(DSUB6-Pad1)") (class "Default")
      (node (ref "DSUB6") (pin "1") (pinfunction "1_1") (pintype "passive"))
    )
    (net (code "126") (name "unconnected-(DSUB6-Pad4)") (class "Default")
      (node (ref "DSUB6") (pin "4") (pinfunction "4_4") (pintype "passive"))
    )
    (net (code "127") (name "unconnected-(DSUB6-Pad6)") (class "Default")
      (node (ref "DSUB6") (pin "6") (pinfunction "6_6") (pintype "passive"))
    )
    (net (code "128") (name "unconnected-(DSUB6-Pad7)") (class "Default")
      (node (ref "DSUB6") (pin "7") (pinfunction "7_7") (pintype "passive"))
    )
    (net (code "129") (name "unconnected-(DSUB6-Pad8)") (class "Default")
      (node (ref "DSUB6") (pin "8") (pinfunction "8_8") (pintype "passive"))
    )
    (net (code "130") (name "unconnected-(DSUB6-Pad9)") (class "Default")
      (node (ref "DSUB6") (pin "9") (pinfunction "9_9") (pintype "passive"))
    )
    (net (code "131") (name "unconnected-(DSUB7-MH1-Pad10)") (class "Default")
      (node (ref "DSUB7") (pin "10") (pinfunction "MH1_10") (pintype "passive"))
    )
    (net (code "132") (name "unconnected-(DSUB7-MH2-Pad11)") (class "Default")
      (node (ref "DSUB7") (pin "11") (pinfunction "MH2_11") (pintype "passive"))
    )
    (net (code "133") (name "unconnected-(DSUB7-Pad1)") (class "Default")
      (node (ref "DSUB7") (pin "1") (pinfunction "1_1") (pintype "passive"))
    )
    (net (code "134") (name "unconnected-(DSUB7-Pad4)") (class "Default")
      (node (ref "DSUB7") (pin "4") (pinfunction "4_4") (pintype "passive"))
    )
    (net (code "135") (name "unconnected-(DSUB7-Pad6)") (class "Default")
      (node (ref "DSUB7") (pin "6") (pinfunction "6_6") (pintype "passive"))
    )
    (net (code "136") (name "unconnected-(DSUB7-Pad7)") (class "Default")
      (node (ref "DSUB7") (pin "7") (pinfunction "7_7") (pintype "passive"))
    )
    (net (code "137") (name "unconnected-(DSUB7-Pad8)") (class "Default")
      (node (ref "DSUB7") (pin "8") (pinfunction "8_8") (pintype "passive"))
    )
    (net (code "138") (name "unconnected-(DSUB7-Pad9)") (class "Default")
      (node (ref "DSUB7") (pin "9") (pinfunction "9_9") (pintype "passive"))
    )
    (net (code "139") (name "unconnected-(DSUB8-MH1-Pad10)") (class "Default")
      (node (ref "DSUB8") (pin "10") (pinfunction "MH1_10") (pintype "passive"))
    )
    (net (code "140") (name "unconnected-(DSUB8-MH2-Pad11)") (class "Default")
      (node (ref "DSUB8") (pin "11") (pinfunction "MH2_11") (pintype "passive"))
    )
    (net (code "141") (name "unconnected-(DSUB8-Pad1)") (class "Default")
      (node (ref "DSUB8") (pin "1") (pinfunction "1_1") (pintype "passive"))
    )
    (net (code "142") (name "unconnected-(DSUB8-Pad4)") (class "Default")
      (node (ref "DSUB8") (pin "4") (pinfunction "4_4") (pintype "passive"))
    )
    (net (code "143") (name "unconnected-(DSUB8-Pad6)") (class "Default")
      (node (ref "DSUB8") (pin "6") (pinfunction "6_6") (pintype "passive"))
    )
    (net (code "144") (name "unconnected-(DSUB8-Pad7)") (class "Default")
      (node (ref "DSUB8") (pin "7") (pinfunction "7_7") (pintype "passive"))
    )
    (net (code "145") (name "unconnected-(DSUB8-Pad8)") (class "Default")
      (node (ref "DSUB8") (pin "8") (pinfunction "8_8") (pintype "passive"))
    )
    (net (code "146") (name "unconnected-(DSUB8-Pad9)") (class "Default")
      (node (ref "DSUB8") (pin "9") (pinfunction "9_9") (pintype "passive"))
    )
    (net (code "147") (name "unconnected-(U1-R2IN-Pad8)") (class "Default")
      (node (ref "U1") (pin "8") (pinfunction "R2IN_8") (pintype "passive"))
    )
    (net (code "148") (name "unconnected-(U1-R2OUT-Pad9)") (class "Default")
      (node (ref "U1") (pin "9") (pinfunction "R2OUT_9") (pintype "passive"))
    )
    (net (code "149") (name "unconnected-(U1-T2IN-Pad10)") (class "Default")
      (node (ref "U1") (pin "10") (pinfunction "T2IN_10") (pintype "passive"))
    )
    (net (code "150") (name "unconnected-(U1-T2OUT-Pad7)") (class "Default")
      (node (ref "U1") (pin "7") (pinfunction "T2OUT_7") (pintype "passive"))
    )
    (net (code "151") (name "unconnected-(U2-R2IN-Pad8)") (class "Default")
      (node (ref "U2") (pin "8") (pinfunction "R2IN_8") (pintype "passive"))
    )
    (net (code "152") (name "unconnected-(U2-R2OUT-Pad9)") (class "Default")
      (node (ref "U2") (pin "9") (pinfunction "R2OUT_9") (pintype "passive"))
    )
    (net (code "153") (name "unconnected-(U2-T2IN-Pad10)") (class "Default")
      (node (ref "U2") (pin "10") (pinfunction "T2IN_10") (pintype "passive"))
    )
    (net (code "154") (name "unconnected-(U2-T2OUT-Pad7)") (class "Default")
      (node (ref "U2") (pin "7") (pinfunction "T2OUT_7") (pintype "passive"))
    )
    (net (code "155") (name "unconnected-(U3-R2IN-Pad8)") (class "Default")
      (node (ref "U3") (pin "8") (pinfunction "R2IN_8") (pintype "passive"))
    )
    (net (code "156") (name "unconnected-(U3-R2OUT-Pad9)") (class "Default")
      (node (ref "U3") (pin "9") (pinfunction "R2OUT_9") (pintype "passive"))
    )
    (net (code "157") (name "unconnected-(U3-T2IN-Pad10)") (class "Default")
      (node (ref "U3") (pin "10") (pinfunction "T2IN_10") (pintype "passive"))
    )
    (net (code "158") (name "unconnected-(U3-T2OUT-Pad7)") (class "Default")
      (node (ref "U3") (pin "7") (pinfunction "T2OUT_7") (pintype "passive"))
    )
    (net (code "159") (name "unconnected-(U4-R2IN-Pad8)") (class "Default")
      (node (ref "U4") (pin "8") (pinfunction "R2IN_8") (pintype "passive"))
    )
    (net (code "160") (name "unconnected-(U4-R2OUT-Pad9)") (class "Default")
      (node (ref "U4") (pin "9") (pinfunction "R2OUT_9") (pintype "passive"))
    )
    (net (code "161") (name "unconnected-(U4-T2IN-Pad10)") (class "Default")
      (node (ref "U4") (pin "10") (pinfunction "T2IN_10") (pintype "passive"))
    )
    (net (code "162") (name "unconnected-(U4-T2OUT-Pad7)") (class "Default")
      (node (ref "U4") (pin "7") (pinfunction "T2OUT_7") (pintype "passive"))
    )
    (net (code "163") (name "unconnected-(U5-R2IN-Pad8)") (class "Default")
      (node (ref "U5") (pin "8") (pinfunction "R2IN_8") (pintype "passive"))
    )
    (net (code "164") (name "unconnected-(U5-R2OUT-Pad9)") (class "Default")
      (node (ref "U5") (pin "9") (pinfunction "R2OUT_9") (pintype "passive"))
    )
    (net (code "165") (name "unconnected-(U5-T2IN-Pad10)") (class "Default")
      (node (ref "U5") (pin "10") (pinfunction "T2IN_10") (pintype "passive"))
    )
    (net (code "166") (name "unconnected-(U5-T2OUT-Pad7)") (class "Default")
      (node (ref "U5") (pin "7") (pinfunction "T2OUT_7") (pintype "passive"))
    )
    (net (code "167") (name "unconnected-(U6-R2IN-Pad8)") (class "Default")
      (node (ref "U6") (pin "8") (pinfunction "R2IN_8") (pintype "passive"))
    )
    (net (code "168") (name "unconnected-(U6-R2OUT-Pad9)") (class "Default")
      (node (ref "U6") (pin "9") (pinfunction "R2OUT_9") (pintype "passive"))
    )
    (net (code "169") (name "unconnected-(U6-T2IN-Pad10)") (class "Default")
      (node (ref "U6") (pin "10") (pinfunction "T2IN_10") (pintype "passive"))
    )
    (net (code "170") (name "unconnected-(U6-T2OUT-Pad7)") (class "Default")
      (node (ref "U6") (pin "7") (pinfunction "T2OUT_7") (pintype "passive"))
    )
    (net (code "171") (name "unconnected-(U7-R2IN-Pad8)") (class "Default")
      (node (ref "U7") (pin "8") (pinfunction "R2IN_8") (pintype "passive"))
    )
    (net (code "172") (name "unconnected-(U7-R2OUT-Pad9)") (class "Default")
      (node (ref "U7") (pin "9") (pinfunction "R2OUT_9") (pintype "passive"))
    )
    (net (code "173") (name "unconnected-(U7-T2IN-Pad10)") (class "Default")
      (node (ref "U7") (pin "10") (pinfunction "T2IN_10") (pintype "passive"))
    )
    (net (code "174") (name "unconnected-(U7-T2OUT-Pad7)") (class "Default")
      (node (ref "U7") (pin "7") (pinfunction "T2OUT_7") (pintype "passive"))
    )
    (net (code "175") (name "unconnected-(U8-R2IN-Pad8)") (class "Default")
      (node (ref "U8") (pin "8") (pinfunction "R2IN_8") (pintype "passive"))
    )
    (net (code "176") (name "unconnected-(U8-R2OUT-Pad9)") (class "Default")
      (node (ref "U8") (pin "9") (pinfunction "R2OUT_9") (pintype "passive"))
    )
    (net (code "177") (name "unconnected-(U8-T2IN-Pad10)") (class "Default")
      (node (ref "U8") (pin "10") (pinfunction "T2IN_10") (pintype "passive"))
    )
    (net (code "178") (name "unconnected-(U8-T2OUT-Pad7)") (class "Default")
      (node (ref "U8") (pin "7") (pinfunction "T2OUT_7") (pintype "passive"))
    )
  )
)
